# Atmega-8-Burner.net
KiCad netlist of a schematic drawn in EAGLE
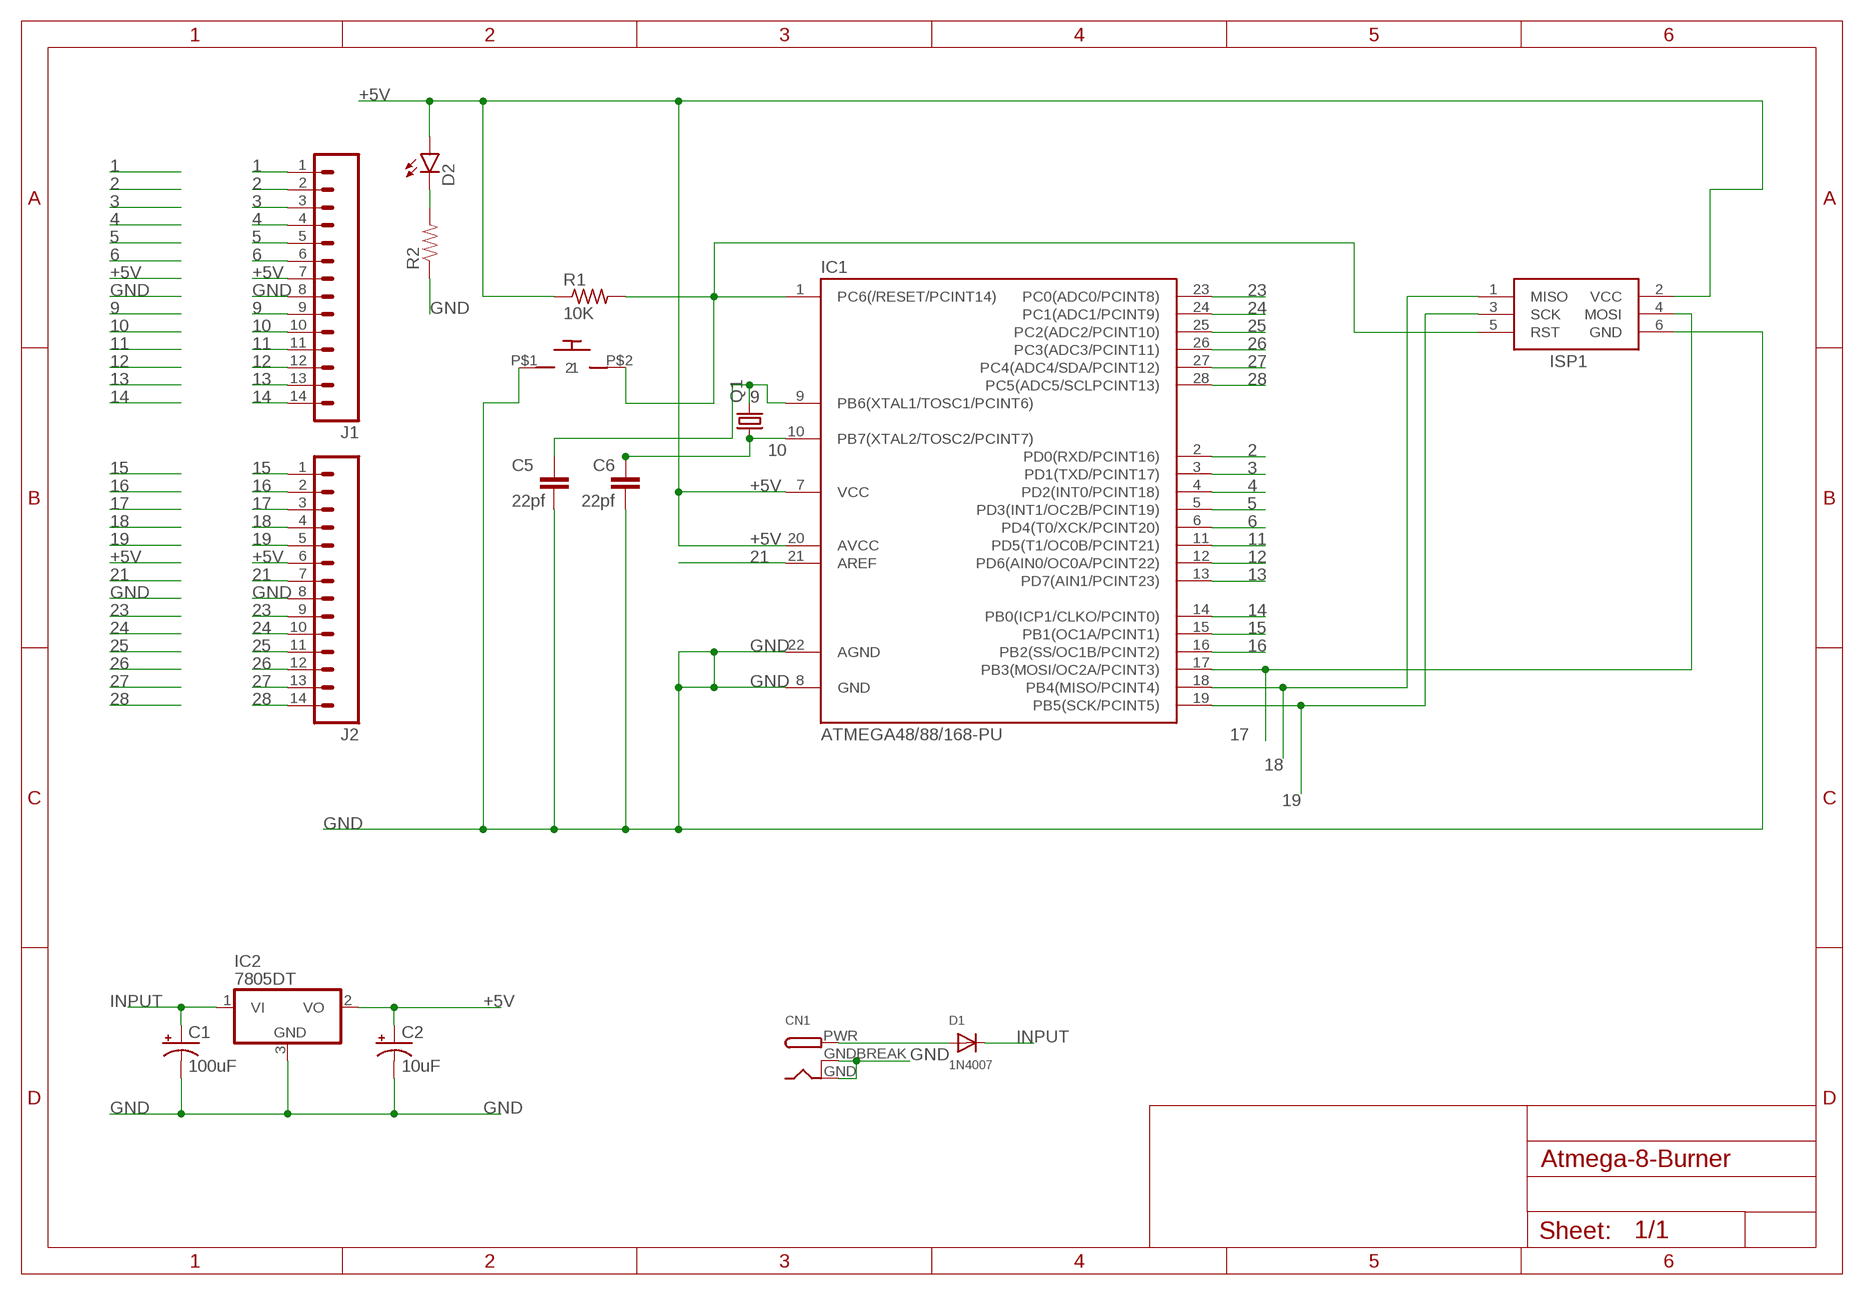
[diagram p0: schematic, sheet 1]

(export (version "E")
  (design (tool "Eeschema 10.0.6"))
  (components
    (comp (ref "C1")
      (value "100uF")
      (footprint "eagle-import:PANASONIC_C")
      (libsource (lib "eagle-import") (part "CAP_POLC"))
    )
    (comp (ref "C2")
      (value "10uF")
      (footprint "eagle-import:PANASONIC_C")
      (libsource (lib "eagle-import") (part "CAP_POLC"))
    )
    (comp (ref "C5")
      (value "22pf")
      (footprint "eagle-import:0603-CAP")
      (libsource (lib "eagle-import") (part "CAP0603-CAP"))
    )
    (comp (ref "C6")
      (value "22pf")
      (footprint "eagle-import:0603-CAP")
      (libsource (lib "eagle-import") (part "CAP0603-CAP"))
    )
    (comp (ref "CN1")
      (value "DCBARRELPTH")
      (footprint "eagle-import:DCJACK_2MM_PTH")
      (libsource (lib "eagle-import") (part "DCBARRELPTH"))
    )
    (comp (ref "D1")
      (value "1N4007")
      (footprint "eagle-import:SMADIODE")
      (libsource (lib "eagle-import") (part "DIODESMA"))
    )
    (comp (ref "D2")
      (value "LED0603")
      (footprint "eagle-import:LED-0603")
      (libsource (lib "eagle-import") (part "LED0603"))
    )
    (comp (ref "IC1")
      (value "ATMEGA48/88/168-PU")
      (footprint "eagle-import:DIL28-3")
      (libsource (lib "eagle-import") (part "ATMEGA48/88/168-PU"))
    )
    (comp (ref "IC2")
      (value "7805DT")
      (footprint "eagle-import:TO252")
      (libsource (lib "eagle-import") (part "78DT05"))
    )
    (comp (ref "ISP1")
      (value "AVRISP-6")
      (footprint "eagle-import:AVRISP")
      (libsource (lib "eagle-import") (part "AVRISP-6"))
    )
    (comp (ref "J1")
      (value "M14LOCK")
      (footprint "eagle-import:1X14_LOCK")
      (libsource (lib "eagle-import") (part "M14LOCK"))
    )
    (comp (ref "J2")
      (value "M14LOCK")
      (footprint "eagle-import:1X14_LOCK")
      (libsource (lib "eagle-import") (part "M14LOCK"))
    )
    (comp (ref "Q1")
      (value "CRYSTALHC49U-V")
      (footprint "eagle-import:HC49U-V")
      (libsource (lib "eagle-import") (part "CRYSTALHC49U-V"))
    )
    (comp (ref "R1")
      (value "10K")
      (footprint "eagle-import:R0603")
      (libsource (lib "eagle-import") (part "R-US_R0603"))
    )
    (comp (ref "R2")
      (value "RESISTOR0603-RES")
      (footprint "eagle-import:0603-RES")
      (libsource (lib "eagle-import") (part "RESISTOR0603-RES"))
    )
    (comp (ref "U$1")
      (value "TAC_SWITCH")
      (footprint "eagle-import:TAC_SWITCH")
      (libsource (lib "eagle-import") (part "TAC_SWITCH"))
    )
  )
  (nets
    (net (code "1") (name "/+5V") (class "Default")
      (node (ref "C2") (pin "+") (pinfunction "+_+") (pintype "passive"))
      (node (ref "D2") (pin "A") (pinfunction "A_A") (pintype "passive"))
      (node (ref "IC1") (pin "20") (pinfunction "AVCC_20") (pintype "passive"))
      (node (ref "IC1") (pin "7") (pinfunction "VCC_7") (pintype "power_in"))
      (node (ref "IC2") (pin "2") (pinfunction "VO_2") (pintype "passive"))
      (node (ref "ISP1") (pin "2") (pinfunction "VCC_2") (pintype "power_in"))
      (node (ref "J1") (pin "7") (pinfunction "7_7") (pintype "passive"))
      (node (ref "J2") (pin "6") (pinfunction "6_6") (pintype "passive"))
      (node (ref "R1") (pin "1") (pinfunction "1_1") (pintype "passive"))
    )
    (net (code "2") (name "/1") (class "Default")
      (node (ref "IC1") (pin "1") (pinfunction "PC6(/RESET/PCINT14)_1") (pintype "bidirectional"))
      (node (ref "ISP1") (pin "5") (pinfunction "RST_5") (pintype "output"))
      (node (ref "J1") (pin "1") (pinfunction "1_1") (pintype "passive"))
      (node (ref "R1") (pin "2") (pinfunction "2_2") (pintype "passive"))
      (node (ref "U$1") (pin "P$2") (pinfunction "2_P$2") (pintype "bidirectional"))
    )
    (net (code "3") (name "/2") (class "Default")
      (node (ref "IC1") (pin "2") (pinfunction "PD0(RXD/PCINT16)_2") (pintype "bidirectional"))
      (node (ref "J1") (pin "2") (pinfunction "2_2") (pintype "passive"))
    )
    (net (code "4") (name "/3") (class "Default")
      (node (ref "IC1") (pin "3") (pinfunction "PD1(TXD/PCINT17)_3") (pintype "bidirectional"))
      (node (ref "J1") (pin "3") (pinfunction "3_3") (pintype "passive"))
    )
    (net (code "5") (name "/4") (class "Default")
      (node (ref "IC1") (pin "4") (pinfunction "PD2(INT0/PCINT18)_4") (pintype "bidirectional"))
      (node (ref "J1") (pin "4") (pinfunction "4_4") (pintype "passive"))
    )
    (net (code "6") (name "/5") (class "Default")
      (node (ref "IC1") (pin "5") (pinfunction "PD3(INT1/OC2B/PCINT19)_5") (pintype "bidirectional"))
      (node (ref "J1") (pin "5") (pinfunction "5_5") (pintype "passive"))
    )
    (net (code "7") (name "/6") (class "Default")
      (node (ref "IC1") (pin "6") (pinfunction "PD4(T0/XCK/PCINT20)_6") (pintype "bidirectional"))
      (node (ref "J1") (pin "6") (pinfunction "6_6") (pintype "passive"))
    )
    (net (code "8") (name "/9") (class "Default")
      (node (ref "C5") (pin "1") (pinfunction "1_1") (pintype "passive"))
      (node (ref "IC1") (pin "9") (pinfunction "PB6(XTAL1/TOSC1/PCINT6)_9") (pintype "bidirectional"))
      (node (ref "J1") (pin "9") (pinfunction "9_9") (pintype "passive"))
      (node (ref "Q1") (pin "2") (pinfunction "2_2") (pintype "passive"))
    )
    (net (code "9") (name "/10") (class "Default")
      (node (ref "C6") (pin "1") (pinfunction "1_1") (pintype "passive"))
      (node (ref "IC1") (pin "10") (pinfunction "PB7(XTAL2/TOSC2/PCINT7)_10") (pintype "bidirectional"))
      (node (ref "J1") (pin "10") (pinfunction "10_10") (pintype "passive"))
      (node (ref "Q1") (pin "1") (pinfunction "1_1") (pintype "passive"))
    )
    (net (code "10") (name "/11") (class "Default")
      (node (ref "IC1") (pin "11") (pinfunction "PD5(T1/OC0B/PCINT21)_11") (pintype "bidirectional"))
      (node (ref "J1") (pin "11") (pinfunction "11_11") (pintype "passive"))
    )
    (net (code "11") (name "/12") (class "Default")
      (node (ref "IC1") (pin "12") (pinfunction "PD6(AIN0/OC0A/PCINT22)_12") (pintype "bidirectional"))
      (node (ref "J1") (pin "12") (pinfunction "12_12") (pintype "passive"))
    )
    (net (code "12") (name "/13") (class "Default")
      (node (ref "IC1") (pin "13") (pinfunction "PD7(AIN1/PCINT23)_13") (pintype "bidirectional"))
      (node (ref "J1") (pin "13") (pinfunction "13_13") (pintype "passive"))
    )
    (net (code "13") (name "/14") (class "Default")
      (node (ref "IC1") (pin "14") (pinfunction "PB0(ICP1/CLKO/PCINT0)_14") (pintype "bidirectional"))
      (node (ref "J1") (pin "14") (pinfunction "14_14") (pintype "passive"))
    )
    (net (code "14") (name "/15") (class "Default")
      (node (ref "IC1") (pin "15") (pinfunction "PB1(OC1A/PCINT1)_15") (pintype "bidirectional"))
      (node (ref "J2") (pin "1") (pinfunction "1_1") (pintype "passive"))
    )
    (net (code "15") (name "/16") (class "Default")
      (node (ref "IC1") (pin "16") (pinfunction "PB2(SS/OC1B/PCINT2)_16") (pintype "bidirectional"))
      (node (ref "J2") (pin "2") (pinfunction "2_2") (pintype "passive"))
    )
    (net (code "16") (name "/17") (class "Default")
      (node (ref "IC1") (pin "17") (pinfunction "PB3(MOSI/OC2A/PCINT3)_17") (pintype "bidirectional"))
      (node (ref "ISP1") (pin "4") (pinfunction "MOSI_4") (pintype "output"))
      (node (ref "J2") (pin "3") (pinfunction "3_3") (pintype "passive"))
    )
    (net (code "17") (name "/18") (class "Default")
      (node (ref "IC1") (pin "18") (pinfunction "PB4(MISO/PCINT4)_18") (pintype "bidirectional"))
      (node (ref "ISP1") (pin "1") (pinfunction "MISO_1") (pintype "input"))
      (node (ref "J2") (pin "4") (pinfunction "4_4") (pintype "passive"))
    )
    (net (code "18") (name "/19") (class "Default")
      (node (ref "IC1") (pin "19") (pinfunction "PB5(SCK/PCINT5)_19") (pintype "bidirectional"))
      (node (ref "ISP1") (pin "3") (pinfunction "SCK_3") (pintype "output"))
      (node (ref "J2") (pin "5") (pinfunction "5_5") (pintype "passive"))
    )
    (net (code "19") (name "/21") (class "Default")
      (node (ref "IC1") (pin "21") (pinfunction "AREF_21") (pintype "passive"))
      (node (ref "J2") (pin "7") (pinfunction "7_7") (pintype "passive"))
    )
    (net (code "20") (name "/23") (class "Default")
      (node (ref "IC1") (pin "23") (pinfunction "PC0(ADC0/PCINT8)_23") (pintype "bidirectional"))
      (node (ref "J2") (pin "9") (pinfunction "9_9") (pintype "passive"))
    )
    (net (code "21") (name "/24") (class "Default")
      (node (ref "IC1") (pin "24") (pinfunction "PC1(ADC1/PCINT9)_24") (pintype "bidirectional"))
      (node (ref "J2") (pin "10") (pinfunction "10_10") (pintype "passive"))
    )
    (net (code "22") (name "/25") (class "Default")
      (node (ref "IC1") (pin "25") (pinfunction "PC2(ADC2/PCINT10)_25") (pintype "bidirectional"))
      (node (ref "J2") (pin "11") (pinfunction "11_11") (pintype "passive"))
    )
    (net (code "23") (name "/26") (class "Default")
      (node (ref "IC1") (pin "26") (pinfunction "PC3(ADC3/PCINT11)_26") (pintype "bidirectional"))
      (node (ref "J2") (pin "12") (pinfunction "12_12") (pintype "passive"))
    )
    (net (code "24") (name "/27") (class "Default")
      (node (ref "IC1") (pin "27") (pinfunction "PC4(ADC4/SDA/PCINT12)_27") (pintype "bidirectional"))
      (node (ref "J2") (pin "13") (pinfunction "13_13") (pintype "passive"))
    )
    (net (code "25") (name "/28") (class "Default")
      (node (ref "IC1") (pin "28") (pinfunction "PC5(ADC5/SCLPCINT13)_28") (pintype "bidirectional"))
      (node (ref "J2") (pin "14") (pinfunction "14_14") (pintype "passive"))
    )
    (net (code "26") (name "/GND") (class "Default")
      (node (ref "C1") (pin "-") (pinfunction "-_-") (pintype "passive"))
      (node (ref "C2") (pin "-") (pinfunction "-_-") (pintype "passive"))
      (node (ref "C5") (pin "2") (pinfunction "2_2") (pintype "passive"))
      (node (ref "C6") (pin "2") (pinfunction "2_2") (pintype "passive"))
      (node (ref "CN1") (pin "GND") (pinfunction "GND_GND") (pintype "power_in"))
      (node (ref "CN1") (pin "GNDBREAK") (pinfunction "GNDBREAK_GNDBREAK") (pintype "power_in"))
      (node (ref "IC1") (pin "22") (pinfunction "AGND_22") (pintype "power_in"))
      (node (ref "IC1") (pin "8") (pinfunction "GND_8") (pintype "power_in"))
      (node (ref "IC2") (pin "3") (pinfunction "GND_3") (pintype "passive"))
      (node (ref "ISP1") (pin "6") (pinfunction "GND_6") (pintype "power_in"))
      (node (ref "J1") (pin "8") (pinfunction "8_8") (pintype "passive"))
      (node (ref "J2") (pin "8") (pinfunction "8_8") (pintype "passive"))
      (node (ref "R2") (pin "1") (pinfunction "1_1") (pintype "passive"))
      (node (ref "U$1") (pin "P$1") (pinfunction "1_P$1") (pintype "bidirectional"))
    )
    (net (code "27") (name "/INPUT") (class "Default")
      (node (ref "C1") (pin "+") (pinfunction "+_+") (pintype "passive"))
      (node (ref "D1") (pin "C") (pinfunction "C_C") (pintype "passive"))
      (node (ref "IC2") (pin "1") (pinfunction "VI_1") (pintype "input"))
    )
    (net (code "28") (name "Net-(CN1-PadPWR)") (class "Default")
      (node (ref "CN1") (pin "PWR") (pinfunction "PWR_PWR") (pintype "power_in"))
      (node (ref "D1") (pin "A") (pinfunction "A_A") (pintype "passive"))
    )
    (net (code "29") (name "Net-(D2-PadC)") (class "Default")
      (node (ref "D2") (pin "C") (pinfunction "C_C") (pintype "passive"))
      (node (ref "R2") (pin "2") (pinfunction "2_2") (pintype "passive"))
    )
  )
)
